# 16-bit-OV7670_mini_Camera_wing.net
KiCad netlist of a schematic drawn in EAGLE
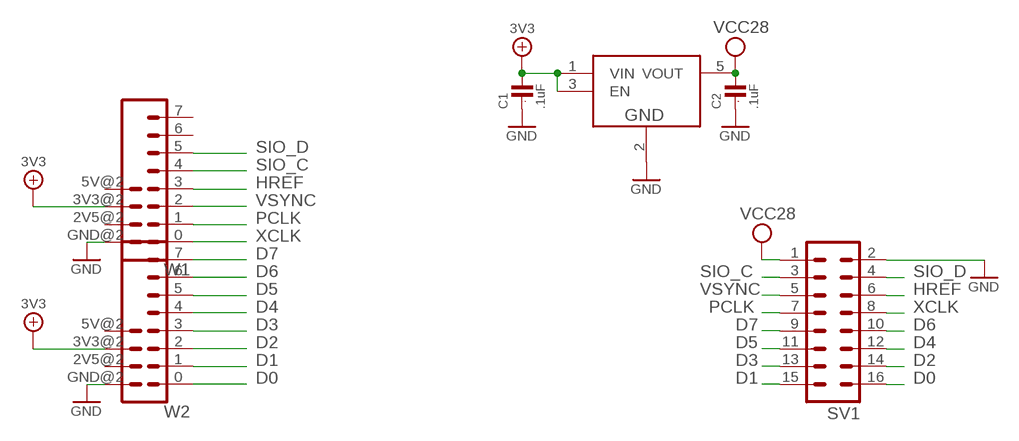
[diagram p0: schematic, sheet 1]

(export (version "E")
  (design (tool "Eeschema 10.0.6"))
  (components
    (comp (ref "C1")
      (value ".1uF")
      (footprint "eagle-import:0603")
      (fields (field (name "PARTNO") "GRM188F51E104ZA01D"))
      (libsource (lib "eagle-import") (part "C0603"))
    )
    (comp (ref "C2")
      (value ".1uF")
      (footprint "eagle-import:0603")
      (fields (field (name "PARTNO") "GRM188F51E104ZA01D"))
      (libsource (lib "eagle-import") (part "C0603"))
    )
    (comp (ref "SV1")
      (value "ML16")
      (footprint "eagle-import:ML16")
      (fields (field (name "PARTNO") "PRPC004DAAN-RC"))
      (libsource (lib "eagle-import") (part "ML16"))
    )
    (comp (ref "U1")
      (value "TPS73028")
      (footprint "eagle-import:SOT23-DBV")
      (fields (field (name "PARTNO") "TPS73028DBVT"))
      (libsource (lib "eagle-import") (part "LP3990MF"))
    )
    (comp (ref "W1")
      (value "WING8WING8_NOHOLES")
      (footprint "eagle-import:WINGSIDE_8BIT_NOHOLES")
      (fields (field (name "PARTNO") "68001-112HLF"))
      (libsource (lib "eagle-import") (part "WING8WING8_NOHOLES"))
    )
    (comp (ref "W2")
      (value "WING8WING8_NOHOLES")
      (footprint "eagle-import:WINGSIDE_8BIT_NOHOLES")
      (fields (field (name "PARTNO") "68001-112HLF"))
      (libsource (lib "eagle-import") (part "WING8WING8_NOHOLES"))
    )
  )
  (nets
    (net (code "1") (name "/D0") (class "Default")
      (node (ref "SV1") (pin "16") (pinfunction "16_16") (pintype "passive"))
      (node (ref "W2") (pin "0") (pinfunction "1_0") (pintype "passive"))
    )
    (net (code "2") (name "/D1") (class "Default")
      (node (ref "SV1") (pin "15") (pinfunction "15_15") (pintype "passive"))
      (node (ref "W2") (pin "1") (pinfunction "2_1") (pintype "passive"))
    )
    (net (code "3") (name "/D2") (class "Default")
      (node (ref "SV1") (pin "14") (pinfunction "14_14") (pintype "passive"))
      (node (ref "W2") (pin "2") (pinfunction "3_2") (pintype "passive"))
    )
    (net (code "4") (name "/D3") (class "Default")
      (node (ref "SV1") (pin "13") (pinfunction "13_13") (pintype "passive"))
      (node (ref "W2") (pin "3") (pinfunction "4_3") (pintype "passive"))
    )
    (net (code "5") (name "/D4") (class "Default")
      (node (ref "SV1") (pin "12") (pinfunction "12_12") (pintype "passive"))
      (node (ref "W2") (pin "4") (pinfunction "5_4") (pintype "passive"))
    )
    (net (code "6") (name "/D5") (class "Default")
      (node (ref "SV1") (pin "11") (pinfunction "11_11") (pintype "passive"))
      (node (ref "W2") (pin "5") (pinfunction "6_5") (pintype "passive"))
    )
    (net (code "7") (name "/D6") (class "Default")
      (node (ref "SV1") (pin "10") (pinfunction "10_10") (pintype "passive"))
      (node (ref "W2") (pin "6") (pinfunction "7_6") (pintype "passive"))
    )
    (net (code "8") (name "/D7") (class "Default")
      (node (ref "SV1") (pin "9") (pinfunction "9_9") (pintype "passive"))
      (node (ref "W2") (pin "7") (pinfunction "8_7") (pintype "passive"))
    )
    (net (code "9") (name "/HREF") (class "Default")
      (node (ref "SV1") (pin "6") (pinfunction "6_6") (pintype "passive"))
      (node (ref "W1") (pin "3") (pinfunction "4_3") (pintype "passive"))
    )
    (net (code "10") (name "/PCLK") (class "Default")
      (node (ref "SV1") (pin "7") (pinfunction "7_7") (pintype "passive"))
      (node (ref "W1") (pin "1") (pinfunction "2_1") (pintype "passive"))
    )
    (net (code "11") (name "/SIO_C") (class "Default")
      (node (ref "SV1") (pin "3") (pinfunction "3_3") (pintype "passive"))
      (node (ref "W1") (pin "4") (pinfunction "5_4") (pintype "passive"))
    )
    (net (code "12") (name "/SIO_D") (class "Default")
      (node (ref "SV1") (pin "4") (pinfunction "4_4") (pintype "passive"))
      (node (ref "W1") (pin "5") (pinfunction "6_5") (pintype "passive"))
    )
    (net (code "13") (name "/VSYNC") (class "Default")
      (node (ref "SV1") (pin "5") (pinfunction "5_5") (pintype "passive"))
      (node (ref "W1") (pin "2") (pinfunction "3_2") (pintype "passive"))
    )
    (net (code "14") (name "/XCLK") (class "Default")
      (node (ref "SV1") (pin "8") (pinfunction "8_8") (pintype "passive"))
      (node (ref "W1") (pin "0") (pinfunction "1_0") (pintype "passive"))
    )
    (net (code "15") (name "3V3") (class "Default")
      (node (ref "C1") (pin "2") (pinfunction "2_2") (pintype "passive"))
      (node (ref "U1") (pin "1") (pinfunction "VIN_1") (pintype "bidirectional"))
      (node (ref "U1") (pin "3") (pinfunction "EN_3") (pintype "bidirectional"))
      (node (ref "W1") (pin "3V3@2") (pinfunction "3V3_3V3@2") (pintype "passive"))
      (node (ref "W2") (pin "3V3@2") (pinfunction "3V3_3V3@2") (pintype "passive"))
    )
    (net (code "16") (name "GND") (class "Default")
      (node (ref "C1") (pin "1") (pinfunction "1_1") (pintype "passive"))
      (node (ref "C2") (pin "1") (pinfunction "1_1") (pintype "passive"))
      (node (ref "SV1") (pin "2") (pinfunction "2_2") (pintype "passive"))
      (node (ref "U1") (pin "2") (pinfunction "GND_2") (pintype "bidirectional"))
      (node (ref "W1") (pin "GND@2") (pinfunction "GND_GND@2") (pintype "passive"))
      (node (ref "W2") (pin "GND@2") (pinfunction "GND_GND@2") (pintype "passive"))
    )
    (net (code "17") (name "VCC28") (class "Default")
      (node (ref "C2") (pin "2") (pinfunction "2_2") (pintype "passive"))
      (node (ref "SV1") (pin "1") (pinfunction "1_1") (pintype "passive"))
      (node (ref "U1") (pin "5") (pinfunction "VOUT_5") (pintype "bidirectional"))
    )
    (net (code "18") (name "unconnected-(U1-NC-Pad4)") (class "Default")
      (node (ref "U1") (pin "4") (pinfunction "NC_4") (pintype "no_connect"))
    )
    (net (code "19") (name "unconnected-(W1-2V5-Pad2V5@2)") (class "Default")
      (node (ref "W1") (pin "2V5@2") (pinfunction "2V5_2V5@2") (pintype "passive"))
    )
    (net (code "20") (name "unconnected-(W1-5V-Pad5V@2)") (class "Default")
      (node (ref "W1") (pin "5V@2") (pinfunction "5V_5V@2") (pintype "passive"))
    )
    (net (code "21") (name "unconnected-(W1-7-Pad6)") (class "Default")
      (node (ref "W1") (pin "6") (pinfunction "7_6") (pintype "passive"))
    )
    (net (code "22") (name "unconnected-(W1-8-Pad7)") (class "Default")
      (node (ref "W1") (pin "7") (pinfunction "8_7") (pintype "passive"))
    )
    (net (code "23") (name "unconnected-(W2-2V5-Pad2V5@2)") (class "Default")
      (node (ref "W2") (pin "2V5@2") (pinfunction "2V5_2V5@2") (pintype "passive"))
    )
    (net (code "24") (name "unconnected-(W2-5V-Pad5V@2)") (class "Default")
      (node (ref "W2") (pin "5V@2") (pinfunction "5V_5V@2") (pintype "passive"))
    )
  )
)
